# LED.net
KiCad netlist of a schematic drawn in Altium Designer
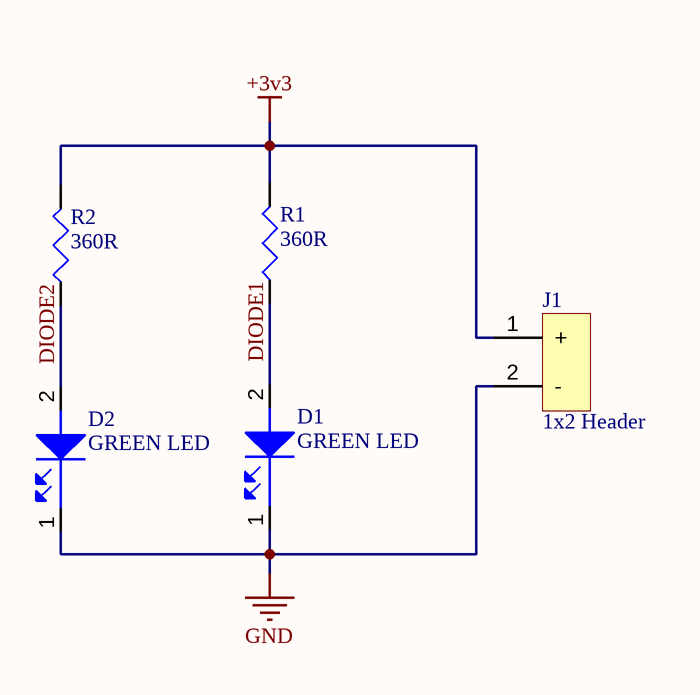
[diagram p0: LED.SchDoc]

(export (version "E")
  (design (tool "Eeschema 10.0.6"))
  (components
    (comp (ref "D1")
      (value "GREEN LED")
      (footprint "LED0603G")
      (description "LED GREEN 0603 SMD")
      (fields
        (field (name "MANUFACTURER") "Panasonic SSG")
        (field (name "MANUFACTURER PART NUMBER") "LNJ337W83RA")
      )
      (libsource (lib "LED_Schlib") (part "LNJ337W83RA"))
    )
    (comp (ref "D2")
      (value "GREEN LED")
      (footprint "LED0603G")
      (description "LED GREEN 0603 SMD")
      (fields
        (field (name "MANUFACTURER") "Panasonic SSG")
        (field (name "MANUFACTURER PART NUMBER") "LNJ337W83RA")
      )
      (libsource (lib "LED_Schlib") (part "LNJ337W83RA"))
    )
    (comp (ref "J1")
      (value "1x2 Header")
      (footprint "HEADER1x2")
      (description "KK 254 Wire-to-Board Header, Vertical, with Friction Lock, 2 Circuits, Gold (Au) Plating")
      (fields (field (name "MANUFACTURER") "Molex") (field (name "MANUFACTURER PART NUMBER") "22-29-2021"))
      (libsource (lib "LED_Schlib") (part "22-29-2021"))
    )
    (comp (ref "R1")
      (value "360R")
      (footprint "R0805")
      (description "Res Thick Film 0805 360 Ohm 1% 1/8W ±100ppm/°C Molded SMD SMD Paper T/R")
      (fields
        (field (name "MANUFACTURER") "Vishay")
        (field (name "MANUFACTURER PART NUMBER") "CRCW0805360RFKEA")
      )
      (libsource (lib "LED_Schlib") (part "CRCW0805360RFKEA"))
    )
    (comp (ref "R2")
      (value "360R")
      (footprint "R0805")
      (description "Res Thick Film 0805 360 Ohm 1% 1/8W ±100ppm/°C Molded SMD SMD Paper T/R")
      (fields
        (field (name "MANUFACTURER") "Vishay")
        (field (name "MANUFACTURER PART NUMBER") "CRCW0805360RFKEA")
      )
      (libsource (lib "LED_Schlib") (part "CRCW0805360RFKEA"))
    )
  )
  (nets
    (net (code "1") (name "+3v3") (class "Default")
      (node (ref "J1") (pin "1") (pinfunction "+_1") (pintype "passive"))
      (node (ref "R1") (pin "2") (pinfunction "2_2") (pintype "passive"))
      (node (ref "R2") (pin "2") (pinfunction "2_2") (pintype "passive"))
    )
    (net (code "2") (name "/DIODE1") (class "Default")
      (node (ref "D1") (pin "2") (pinfunction "2_2") (pintype "passive"))
      (node (ref "R1") (pin "1") (pinfunction "1_1") (pintype "passive"))
    )
    (net (code "3") (name "/DIODE2") (class "Default")
      (node (ref "D2") (pin "2") (pinfunction "2_2") (pintype "passive"))
      (node (ref "R2") (pin "1") (pinfunction "1_1") (pintype "passive"))
    )
    (net (code "4") (name "GND") (class "Default")
      (node (ref "D1") (pin "1") (pinfunction "1_1") (pintype "passive"))
      (node (ref "D2") (pin "1") (pinfunction "1_1") (pintype "passive"))
      (node (ref "J1") (pin "2") (pinfunction "-_2") (pintype "passive"))
    )
  )
)
